# unonhietdodoam.net
KiCad netlist of a schematic drawn in Altium Designer
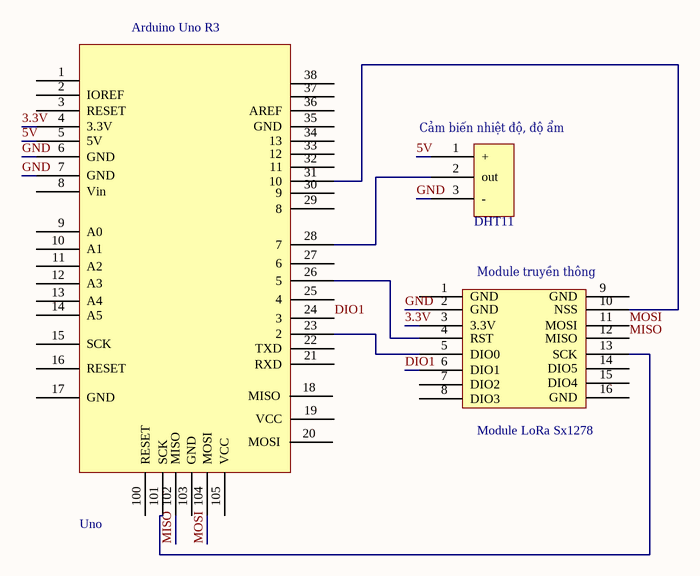
[diagram p0: unonhietdodoam.SchDoc]

(export (version "E")
  (design (tool "Eeschema 10.0.6"))
  (components
    (comp (ref "Arduino Uno R3")
      (value "Uno")
      (footprint "PCBComponent_1")
      (libsource (lib "uno") (part "Uno"))
    )
    (comp (ref "Cảm biến nhiệt độ, độ ẩm")
      (value "DHT11")
      (footprint "PCBDHT11")
      (libsource (lib "dht11") (part "Component_1"))
    )
    (comp (ref "Module truyền thông")
      (value "Module LoRa Sx1278")
      (footprint "PCBLoRa")
      (libsource (lib "LoRa") (part "Component_1"))
    )
  )
  (nets
    (net (code "1") (name "/3.3V") (class "Default")
      (node (ref "Arduino Uno R3") (pin "4") (pinfunction "3.3V_4") (pintype "passive"))
      (node (ref "Module truyền thông") (pin "3") (pinfunction "3.3V_3") (pintype "passive"))
    )
    (net (code "2") (name "/5V") (class "Default")
      (node (ref "Arduino Uno R3") (pin "5") (pinfunction "5V_5") (pintype "passive"))
      (node (ref "Cảm biến nhiệt độ, độ ẩm") (pin "1") (pinfunction "+_1") (pintype "passive"))
    )
    (net (code "3") (name "/DIO1") (class "Default")
      (node (ref "Arduino Uno R3") (pin "24") (pinfunction "3_24") (pintype "passive"))
      (node (ref "Module truyền thông") (pin "6") (pinfunction "DIO1_6") (pintype "passive"))
    )
    (net (code "4") (name "/GND") (class "Default")
      (node (ref "Arduino Uno R3") (pin "6") (pinfunction "GND_6") (pintype "passive"))
      (node (ref "Arduino Uno R3") (pin "7") (pinfunction "GND_7") (pintype "passive"))
      (node (ref "Cảm biến nhiệt độ, độ ẩm") (pin "3") (pinfunction "-_3") (pintype "passive"))
      (node (ref "Module truyền thông") (pin "2") (pinfunction "GND_2") (pintype "passive"))
    )
    (net (code "5") (name "/MISO") (class "Default")
      (node (ref "Arduino Uno R3") (pin "102") (pinfunction "MISO_102") (pintype "passive"))
      (node (ref "Module truyền thông") (pin "12") (pinfunction "MISO_12") (pintype "passive"))
    )
    (net (code "6") (name "/MOSI") (class "Default")
      (node (ref "Arduino Uno R3") (pin "104") (pinfunction "MOSI_104") (pintype "passive"))
      (node (ref "Module truyền thông") (pin "11") (pinfunction "MOSI_11") (pintype "passive"))
    )
    (net (code "7") (name "Net-(Arduino Uno R3-2)") (class "Default")
      (node (ref "Arduino Uno R3") (pin "23") (pinfunction "2_23") (pintype "passive"))
      (node (ref "Module truyền thông") (pin "5") (pinfunction "DIO0_5") (pintype "passive"))
    )
    (net (code "8") (name "Net-(Arduino Uno R3-5)") (class "Default")
      (node (ref "Arduino Uno R3") (pin "26") (pinfunction "5_26") (pintype "passive"))
      (node (ref "Module truyền thông") (pin "4") (pinfunction "RST_4") (pintype "passive"))
    )
    (net (code "9") (name "Net-(Arduino Uno R3-7)") (class "Default")
      (node (ref "Arduino Uno R3") (pin "28") (pinfunction "7_28") (pintype "passive"))
      (node (ref "Cảm biến nhiệt độ, độ ẩm") (pin "2") (pinfunction "out_2") (pintype "passive"))
    )
    (net (code "10") (name "Net-(Arduino Uno R3-10)") (class "Default")
      (node (ref "Arduino Uno R3") (pin "31") (pinfunction "10_31") (pintype "passive"))
      (node (ref "Module truyền thông") (pin "10") (pinfunction "NSS_10") (pintype "passive"))
    )
    (net (code "11") (name "Net-(Module truyền thông-SCK)") (class "Default")
      (node (ref "Arduino Uno R3") (pin "101") (pinfunction "SCK_101") (pintype "passive"))
      (node (ref "Module truyền thông") (pin "13") (pinfunction "SCK_13") (pintype "passive"))
    )
    (net (code "12") (name "unconnected-(Arduino Uno R3-4-Pad25)") (class "Default")
      (node (ref "Arduino Uno R3") (pin "25") (pinfunction "4_25") (pintype "passive"))
    )
    (net (code "13") (name "unconnected-(Arduino Uno R3-6-Pad27)") (class "Default")
      (node (ref "Arduino Uno R3") (pin "27") (pinfunction "6_27") (pintype "passive"))
    )
    (net (code "14") (name "unconnected-(Arduino Uno R3-8-Pad29)") (class "Default")
      (node (ref "Arduino Uno R3") (pin "29") (pinfunction "8_29") (pintype "passive"))
    )
    (net (code "15") (name "unconnected-(Arduino Uno R3-9-Pad30)") (class "Default")
      (node (ref "Arduino Uno R3") (pin "30") (pinfunction "9_30") (pintype "passive"))
    )
    (net (code "16") (name "unconnected-(Arduino Uno R3-11-Pad32)") (class "Default")
      (node (ref "Arduino Uno R3") (pin "32") (pinfunction "11_32") (pintype "passive"))
    )
    (net (code "17") (name "unconnected-(Arduino Uno R3-12-Pad33)") (class "Default")
      (node (ref "Arduino Uno R3") (pin "33") (pinfunction "12_33") (pintype "passive"))
    )
    (net (code "18") (name "unconnected-(Arduino Uno R3-13-Pad34)") (class "Default")
      (node (ref "Arduino Uno R3") (pin "34") (pinfunction "13_34") (pintype "passive"))
    )
    (net (code "19") (name "unconnected-(Arduino Uno R3-A0-Pad9)") (class "Default")
      (node (ref "Arduino Uno R3") (pin "9") (pinfunction "A0_9") (pintype "passive"))
    )
    (net (code "20") (name "unconnected-(Arduino Uno R3-A1-Pad10)") (class "Default")
      (node (ref "Arduino Uno R3") (pin "10") (pinfunction "A1_10") (pintype "passive"))
    )
    (net (code "21") (name "unconnected-(Arduino Uno R3-A2-Pad11)") (class "Default")
      (node (ref "Arduino Uno R3") (pin "11") (pinfunction "A2_11") (pintype "passive"))
    )
    (net (code "22") (name "unconnected-(Arduino Uno R3-A3-Pad12)") (class "Default")
      (node (ref "Arduino Uno R3") (pin "12") (pinfunction "A3_12") (pintype "passive"))
    )
    (net (code "23") (name "unconnected-(Arduino Uno R3-A4-Pad13)") (class "Default")
      (node (ref "Arduino Uno R3") (pin "13") (pinfunction "A4_13") (pintype "passive"))
    )
    (net (code "24") (name "unconnected-(Arduino Uno R3-A5-Pad14)") (class "Default")
      (node (ref "Arduino Uno R3") (pin "14") (pinfunction "A5_14") (pintype "passive"))
    )
    (net (code "25") (name "unconnected-(Arduino Uno R3-AREF-Pad36)") (class "Default")
      (node (ref "Arduino Uno R3") (pin "36") (pinfunction "AREF_36") (pintype "passive"))
    )
    (net (code "26") (name "unconnected-(Arduino Uno R3-GND-Pad17)") (class "Default")
      (node (ref "Arduino Uno R3") (pin "17") (pinfunction "GND_17") (pintype "passive"))
    )
    (net (code "27") (name "unconnected-(Arduino Uno R3-GND-Pad35)") (class "Default")
      (node (ref "Arduino Uno R3") (pin "35") (pinfunction "GND_35") (pintype "passive"))
    )
    (net (code "28") (name "unconnected-(Arduino Uno R3-GND-Pad103)") (class "Default")
      (node (ref "Arduino Uno R3") (pin "103") (pinfunction "GND_103") (pintype "passive"))
    )
    (net (code "29") (name "unconnected-(Arduino Uno R3-IOREF-Pad2)") (class "Default")
      (node (ref "Arduino Uno R3") (pin "2") (pinfunction "IOREF_2") (pintype "passive"))
    )
    (net (code "30") (name "unconnected-(Arduino Uno R3-MISO-Pad18)") (class "Default")
      (node (ref "Arduino Uno R3") (pin "18") (pinfunction "MISO_18") (pintype "passive"))
    )
    (net (code "31") (name "unconnected-(Arduino Uno R3-MOSI-Pad20)") (class "Default")
      (node (ref "Arduino Uno R3") (pin "20") (pinfunction "MOSI_20") (pintype "passive"))
    )
    (net (code "32") (name "unconnected-(Arduino Uno R3-Pad1)") (class "Default")
      (node (ref "Arduino Uno R3") (pin "1") (pintype "passive"))
    )
    (net (code "33") (name "unconnected-(Arduino Uno R3-Pad37)") (class "Default")
      (node (ref "Arduino Uno R3") (pin "37") (pintype "passive"))
    )
    (net (code "34") (name "unconnected-(Arduino Uno R3-Pad38)") (class "Default")
      (node (ref "Arduino Uno R3") (pin "38") (pintype "passive"))
    )
    (net (code "35") (name "unconnected-(Arduino Uno R3-RESET-Pad3)") (class "Default")
      (node (ref "Arduino Uno R3") (pin "3") (pinfunction "RESET_3") (pintype "passive"))
    )
    (net (code "36") (name "unconnected-(Arduino Uno R3-RESET-Pad16)") (class "Default")
      (node (ref "Arduino Uno R3") (pin "16") (pinfunction "RESET_16") (pintype "passive"))
    )
    (net (code "37") (name "unconnected-(Arduino Uno R3-RESET-Pad100)") (class "Default")
      (node (ref "Arduino Uno R3") (pin "100") (pinfunction "RESET_100") (pintype "passive"))
    )
    (net (code "38") (name "unconnected-(Arduino Uno R3-RXD-Pad21)") (class "Default")
      (node (ref "Arduino Uno R3") (pin "21") (pinfunction "RXD_21") (pintype "passive"))
    )
    (net (code "39") (name "unconnected-(Arduino Uno R3-SCK-Pad15)") (class "Default")
      (node (ref "Arduino Uno R3") (pin "15") (pinfunction "SCK_15") (pintype "passive"))
    )
    (net (code "40") (name "unconnected-(Arduino Uno R3-TXD-Pad22)") (class "Default")
      (node (ref "Arduino Uno R3") (pin "22") (pinfunction "TXD_22") (pintype "passive"))
    )
    (net (code "41") (name "unconnected-(Arduino Uno R3-VCC-Pad19)") (class "Default")
      (node (ref "Arduino Uno R3") (pin "19") (pinfunction "VCC_19") (pintype "passive"))
    )
    (net (code "42") (name "unconnected-(Arduino Uno R3-VCC-Pad105)") (class "Default")
      (node (ref "Arduino Uno R3") (pin "105") (pinfunction "VCC_105") (pintype "passive"))
    )
    (net (code "43") (name "unconnected-(Arduino Uno R3-Vin-Pad8)") (class "Default")
      (node (ref "Arduino Uno R3") (pin "8") (pinfunction "Vin_8") (pintype "passive"))
    )
    (net (code "44") (name "unconnected-(Module truyền thông-DIO2-Pad7)") (class "Default")
      (node (ref "Module truyền thông") (pin "7") (pinfunction "DIO2_7") (pintype "passive"))
    )
    (net (code "45") (name "unconnected-(Module truyền thông-DIO3-Pad8)") (class "Default")
      (node (ref "Module truyền thông") (pin "8") (pinfunction "DIO3_8") (pintype "passive"))
    )
    (net (code "46") (name "unconnected-(Module truyền thông-DIO4-Pad15)") (class "Default")
      (node (ref "Module truyền thông") (pin "15") (pinfunction "DIO4_15") (pintype "passive"))
    )
    (net (code "47") (name "unconnected-(Module truyền thông-DIO5-Pad14)") (class "Default")
      (node (ref "Module truyền thông") (pin "14") (pinfunction "DIO5_14") (pintype "passive"))
    )
    (net (code "48") (name "unconnected-(Module truyền thông-GND-Pad1)") (class "Default")
      (node (ref "Module truyền thông") (pin "1") (pinfunction "GND_1") (pintype "passive"))
    )
    (net (code "49") (name "unconnected-(Module truyền thông-GND-Pad9)") (class "Default")
      (node (ref "Module truyền thông") (pin "9") (pinfunction "GND_9") (pintype "passive"))
    )
    (net (code "50") (name "unconnected-(Module truyền thông-GND-Pad16)") (class "Default")
      (node (ref "Module truyền thông") (pin "16") (pinfunction "GND_16") (pintype "passive"))
    )
  )
)
